# rev1.net
KiCad netlist of a schematic drawn in EAGLE
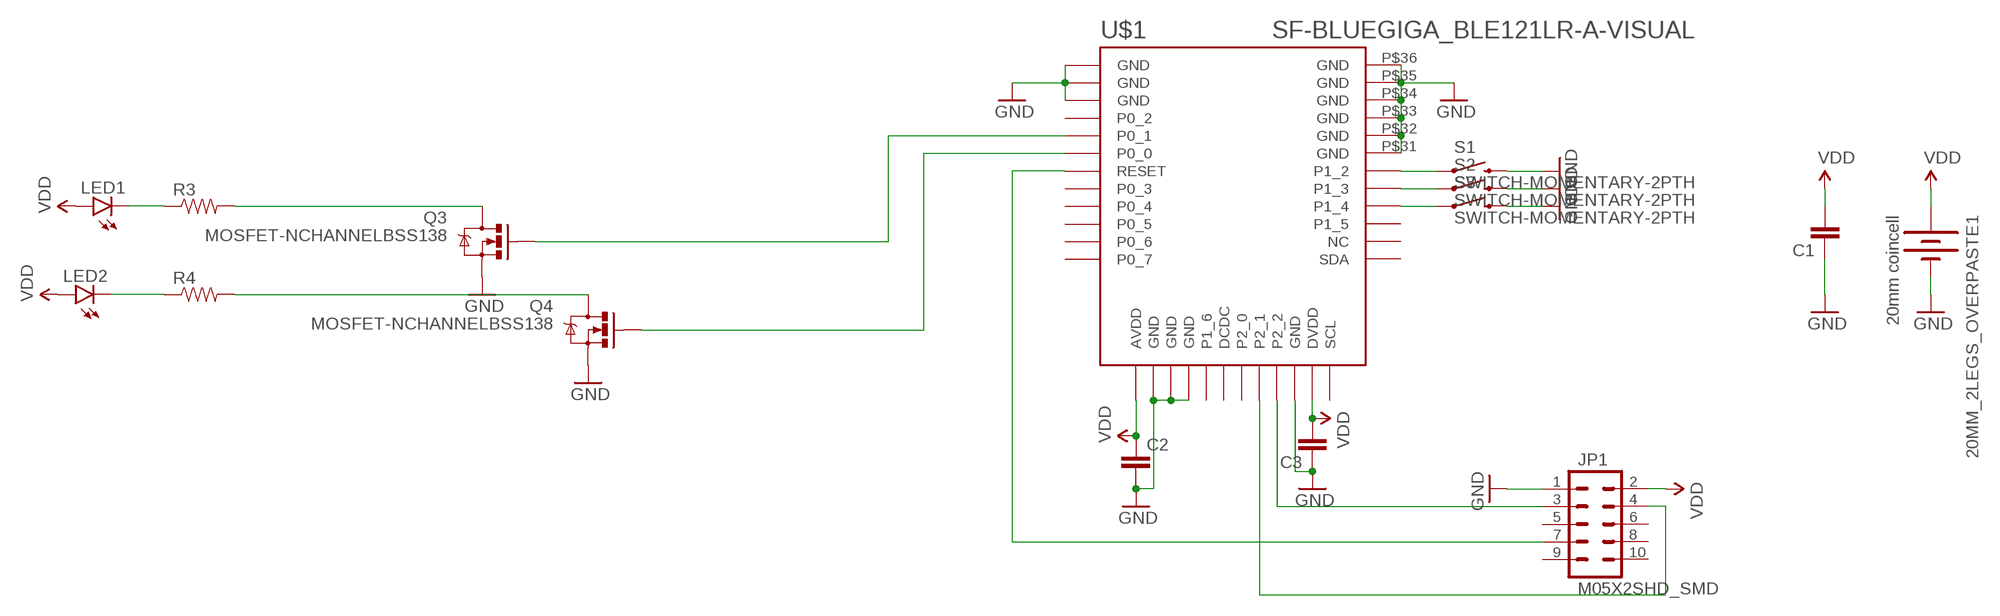
[diagram p0: schematic, sheet 1]

(export (version "E")
  (design (tool "Eeschema 10.0.6"))
  (components
    (comp (ref "20MM_2LEGS_OVERPASTE1")
      (value "20mm coincell")
      (footprint "eagle-import:BATTCON_20MM_4LEGS")
      (libsource (lib "eagle-import") (part "BATTERY20MM_4LEGS"))
    )
    (comp (ref "C1")
      (value "CAP1206")
      (footprint "eagle-import:1206")
      (libsource (lib "eagle-import") (part "CAP1206"))
    )
    (comp (ref "C2")
      (value "CAP0603-CAP")
      (footprint "eagle-import:0603-CAP")
      (libsource (lib "eagle-import") (part "CAP0603-CAP"))
    )
    (comp (ref "C3")
      (value "CAP0603-CAP")
      (footprint "eagle-import:0603-CAP")
      (libsource (lib "eagle-import") (part "CAP0603-CAP"))
    )
    (comp (ref "JP1")
      (value "M05X2SHD_SMD")
      (footprint "eagle-import:2X5-SHROUDED_SMD")
      (libsource (lib "eagle-import") (part "M05X2SHD_SMD"))
    )
    (comp (ref "LED1")
      (value "LED1206")
      (footprint "eagle-import:LED-1206")
      (libsource (lib "eagle-import") (part "LED1206"))
    )
    (comp (ref "LED2")
      (value "LED1206")
      (footprint "eagle-import:LED-1206")
      (libsource (lib "eagle-import") (part "LED1206"))
    )
    (comp (ref "Q3")
      (value "MOSFET-NCHANNELBSS138")
      (footprint "eagle-import:SOT23-3")
      (libsource (lib "eagle-import") (part "MOSFET-NCHANNELBSS138"))
    )
    (comp (ref "Q4")
      (value "MOSFET-NCHANNELBSS138")
      (footprint "eagle-import:SOT23-3")
      (libsource (lib "eagle-import") (part "MOSFET-NCHANNELBSS138"))
    )
    (comp (ref "R3")
      (value "RESISTOR0603")
      (footprint "eagle-import:0603-RES")
      (libsource (lib "eagle-import") (part "RESISTOR0603"))
    )
    (comp (ref "R4")
      (value "RESISTOR0603")
      (footprint "eagle-import:0603-RES")
      (libsource (lib "eagle-import") (part "RESISTOR0603"))
    )
    (comp (ref "S1")
      (value "SWITCH-MOMENTARY-2PTH")
      (footprint "eagle-import:TACTILE-PTH")
      (libsource (lib "eagle-import") (part "SWITCH-MOMENTARY-2PTH"))
    )
    (comp (ref "S2")
      (value "SWITCH-MOMENTARY-2PTH")
      (footprint "eagle-import:TACTILE-PTH")
      (libsource (lib "eagle-import") (part "SWITCH-MOMENTARY-2PTH"))
    )
    (comp (ref "S3")
      (value "SWITCH-MOMENTARY-2PTH")
      (footprint "eagle-import:TACTILE-PTH")
      (libsource (lib "eagle-import") (part "SWITCH-MOMENTARY-2PTH"))
    )
    (comp (ref "U$1")
      (value "SF-BLUEGIGA_BLE121LR-A-VISUAL")
      (footprint "eagle-import:SF-BLUEGIGA_BLE121LR-A")
      (libsource (lib "eagle-import") (part "SF-BLUEGIGA_BLE121LR-A-VISUAL"))
    )
  )
  (nets
    (net (code "1") (name "GND") (class "Default")
      (node (ref "20MM_2LEGS_OVERPASTE1") (pin "2") (pinfunction "-_2") (pintype "power_in"))
      (node (ref "C1") (pin "1") (pinfunction "1_1") (pintype "passive"))
      (node (ref "C2") (pin "2") (pinfunction "2_2") (pintype "passive"))
      (node (ref "C3") (pin "1") (pinfunction "1_1") (pintype "passive"))
      (node (ref "JP1") (pin "1") (pinfunction "1_1") (pintype "passive"))
      (node (ref "Q3") (pin "2") (pinfunction "S_2") (pintype "passive"))
      (node (ref "Q4") (pin "2") (pinfunction "S_2") (pintype "passive"))
      (node (ref "S1") (pin "3") (pinfunction "2_3") (pintype "passive"))
      (node (ref "S2") (pin "3") (pinfunction "2_3") (pintype "passive"))
      (node (ref "S3") (pin "3") (pinfunction "2_3") (pintype "passive"))
      (node (ref "U$1") (pin "P$1") (pinfunction "GND_P$1") (pintype "power_in"))
      (node (ref "U$1") (pin "P$14") (pinfunction "GND_P$14") (pintype "power_in"))
      (node (ref "U$1") (pin "P$15") (pinfunction "GND_P$15") (pintype "power_in"))
      (node (ref "U$1") (pin "P$16") (pinfunction "GND_P$16") (pintype "power_in"))
      (node (ref "U$1") (pin "P$2") (pinfunction "GND_P$2") (pintype "power_in"))
      (node (ref "U$1") (pin "P$22") (pinfunction "GND_P$22") (pintype "power_in"))
      (node (ref "U$1") (pin "P$3") (pinfunction "GND_P$3") (pintype "power_in"))
      (node (ref "U$1") (pin "P$31") (pinfunction "GND_P$31") (pintype "power_in"))
      (node (ref "U$1") (pin "P$32") (pinfunction "GND_P$32") (pintype "power_in"))
      (node (ref "U$1") (pin "P$33") (pinfunction "GND_P$33") (pintype "power_in"))
      (node (ref "U$1") (pin "P$34") (pinfunction "GND_P$34") (pintype "power_in"))
      (node (ref "U$1") (pin "P$35") (pinfunction "GND_P$35") (pintype "power_in"))
      (node (ref "U$1") (pin "P$36") (pinfunction "GND_P$36") (pintype "power_in"))
    )
    (net (code "2") (name "Net-(LED1-PadC)") (class "Default")
      (node (ref "LED1") (pin "C") (pinfunction "C_C") (pintype "passive"))
      (node (ref "R3") (pin "1") (pinfunction "1_1") (pintype "passive"))
    )
    (net (code "3") (name "Net-(LED2-PadC)") (class "Default")
      (node (ref "LED2") (pin "C") (pinfunction "C_C") (pintype "passive"))
      (node (ref "R4") (pin "1") (pinfunction "1_1") (pintype "passive"))
    )
    (net (code "4") (name "Net-(Q3-D)") (class "Default")
      (node (ref "Q3") (pin "3") (pinfunction "D_3") (pintype "passive"))
      (node (ref "R3") (pin "2") (pinfunction "2_2") (pintype "passive"))
    )
    (net (code "5") (name "Net-(Q3-G)") (class "Default")
      (node (ref "Q3") (pin "1") (pinfunction "G_1") (pintype "passive"))
      (node (ref "U$1") (pin "P$5") (pinfunction "P0_1_P$5") (pintype "bidirectional"))
    )
    (net (code "6") (name "Net-(Q4-D)") (class "Default")
      (node (ref "Q4") (pin "3") (pinfunction "D_3") (pintype "passive"))
      (node (ref "R4") (pin "2") (pinfunction "2_2") (pintype "passive"))
    )
    (net (code "7") (name "Net-(Q4-G)") (class "Default")
      (node (ref "Q4") (pin "1") (pinfunction "G_1") (pintype "passive"))
      (node (ref "U$1") (pin "P$6") (pinfunction "P0_0_P$6") (pintype "bidirectional"))
    )
    (net (code "8") (name "Net-(U$1-P1_2)") (class "Default")
      (node (ref "S1") (pin "1") (pinfunction "1_1") (pintype "passive"))
      (node (ref "U$1") (pin "P$30") (pinfunction "P1_2_P$30") (pintype "bidirectional"))
    )
    (net (code "9") (name "Net-(U$1-P1_3)") (class "Default")
      (node (ref "S2") (pin "1") (pinfunction "1_1") (pintype "passive"))
      (node (ref "U$1") (pin "P$29") (pinfunction "P1_3_P$29") (pintype "input"))
    )
    (net (code "10") (name "Net-(U$1-P1_4)") (class "Default")
      (node (ref "S3") (pin "1") (pinfunction "1_1") (pintype "passive"))
      (node (ref "U$1") (pin "P$28") (pinfunction "P1_4_P$28") (pintype "bidirectional"))
    )
    (net (code "11") (name "Net-(U$1-P2_1)") (class "Default")
      (node (ref "JP1") (pin "4") (pinfunction "4_4") (pintype "passive"))
      (node (ref "U$1") (pin "P$20") (pinfunction "P2_1_P$20") (pintype "bidirectional"))
    )
    (net (code "12") (name "Net-(U$1-P2_2)") (class "Default")
      (node (ref "JP1") (pin "3") (pinfunction "3_3") (pintype "passive"))
      (node (ref "U$1") (pin "P$21") (pinfunction "P2_2_P$21") (pintype "bidirectional"))
    )
    (net (code "13") (name "Net-(U$1-RESET)") (class "Default")
      (node (ref "JP1") (pin "7") (pinfunction "7_7") (pintype "passive"))
      (node (ref "U$1") (pin "P$7") (pinfunction "RESET_P$7") (pintype "bidirectional"))
    )
    (net (code "14") (name "VDD") (class "Default")
      (node (ref "20MM_2LEGS_OVERPASTE1") (pin "1") (pinfunction "+_1") (pintype "power_in"))
      (node (ref "C1") (pin "2") (pinfunction "2_2") (pintype "passive"))
      (node (ref "C2") (pin "1") (pinfunction "1_1") (pintype "passive"))
      (node (ref "C3") (pin "2") (pinfunction "2_2") (pintype "passive"))
      (node (ref "JP1") (pin "2") (pinfunction "2_2") (pintype "passive"))
      (node (ref "LED1") (pin "A") (pinfunction "A_A") (pintype "passive"))
      (node (ref "LED2") (pin "A") (pinfunction "A_A") (pintype "passive"))
      (node (ref "U$1") (pin "P$13") (pinfunction "AVDD_P$13") (pintype "power_in"))
      (node (ref "U$1") (pin "P$23") (pinfunction "DVDD_P$23") (pintype "power_in"))
    )
    (net (code "15") (name "unconnected-(JP1-Pad5)") (class "Default")
      (node (ref "JP1") (pin "5") (pinfunction "5_5") (pintype "passive"))
    )
    (net (code "16") (name "unconnected-(JP1-Pad6)") (class "Default")
      (node (ref "JP1") (pin "6") (pinfunction "6_6") (pintype "passive"))
    )
    (net (code "17") (name "unconnected-(JP1-Pad8)") (class "Default")
      (node (ref "JP1") (pin "8") (pinfunction "8_8") (pintype "passive"))
    )
    (net (code "18") (name "unconnected-(JP1-Pad9)") (class "Default")
      (node (ref "JP1") (pin "9") (pinfunction "9_9") (pintype "passive"))
    )
    (net (code "19") (name "unconnected-(JP1-Pad10)") (class "Default")
      (node (ref "JP1") (pin "10") (pinfunction "10_10") (pintype "passive"))
    )
    (net (code "20") (name "unconnected-(U$1-DCDC-PadP$18)") (class "Default")
      (node (ref "U$1") (pin "P$18") (pinfunction "DCDC_P$18") (pintype "bidirectional"))
    )
    (net (code "21") (name "unconnected-(U$1-NC-PadP$26)") (class "Default")
      (node (ref "U$1") (pin "P$26") (pinfunction "NC_P$26") (pintype "no_connect"))
    )
    (net (code "22") (name "unconnected-(U$1-P0_2-PadP$4)") (class "Default")
      (node (ref "U$1") (pin "P$4") (pinfunction "P0_2_P$4") (pintype "bidirectional"))
    )
    (net (code "23") (name "unconnected-(U$1-P0_3-PadP$8)") (class "Default")
      (node (ref "U$1") (pin "P$8") (pinfunction "P0_3_P$8") (pintype "bidirectional"))
    )
    (net (code "24") (name "unconnected-(U$1-P0_4-PadP$9)") (class "Default")
      (node (ref "U$1") (pin "P$9") (pinfunction "P0_4_P$9") (pintype "bidirectional"))
    )
    (net (code "25") (name "unconnected-(U$1-P0_5-PadP$10)") (class "Default")
      (node (ref "U$1") (pin "P$10") (pinfunction "P0_5_P$10") (pintype "bidirectional"))
    )
    (net (code "26") (name "unconnected-(U$1-P0_6-PadP$11)") (class "Default")
      (node (ref "U$1") (pin "P$11") (pinfunction "P0_6_P$11") (pintype "bidirectional"))
    )
    (net (code "27") (name "unconnected-(U$1-P0_7-PadP$12)") (class "Default")
      (node (ref "U$1") (pin "P$12") (pinfunction "P0_7_P$12") (pintype "bidirectional"))
    )
    (net (code "28") (name "unconnected-(U$1-P1_5-PadP$27)") (class "Default")
      (node (ref "U$1") (pin "P$27") (pinfunction "P1_5_P$27") (pintype "bidirectional"))
    )
    (net (code "29") (name "unconnected-(U$1-P1_6-PadP$17)") (class "Default")
      (node (ref "U$1") (pin "P$17") (pinfunction "P1_6_P$17") (pintype "bidirectional"))
    )
    (net (code "30") (name "unconnected-(U$1-P2_0-PadP$19)") (class "Default")
      (node (ref "U$1") (pin "P$19") (pinfunction "P2_0_P$19") (pintype "bidirectional"))
    )
    (net (code "31") (name "unconnected-(U$1-SCL-PadP$24)") (class "Default")
      (node (ref "U$1") (pin "P$24") (pinfunction "SCL_P$24") (pintype "bidirectional"))
    )
    (net (code "32") (name "unconnected-(U$1-SDA-PadP$25)") (class "Default")
      (node (ref "U$1") (pin "P$25") (pinfunction "SDA_P$25") (pintype "bidirectional"))
    )
  )
)
